# Processor.net
KiCad netlist of a schematic drawn in Altium Designer
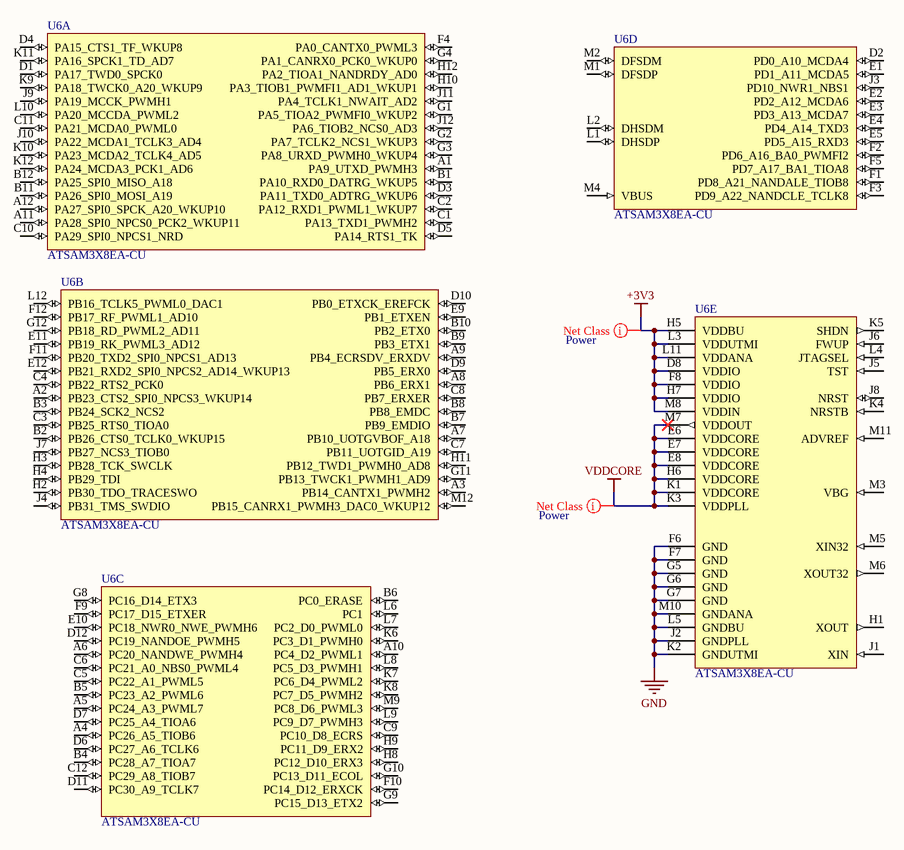
[diagram p0: Processor.SchDoc]

(export (version "E")
  (design (tool "Eeschema 10.0.6"))
  (components
    (comp (ref "U6")
      (value "ATSAM3X8EA-CU")
      (footprint "Atmel_LFBGA144_M")
      (libsource (lib "niceCircuits") (part "ATSAM3X8EA-CU"))
    )
  )
  (nets
    (net (code "1") (name "+3V3") (class "Default")
      (node (ref "U6") (pin "D8") (pinfunction "VDDIO_D8") (pintype "power_in"))
      (node (ref "U6") (pin "F8") (pinfunction "VDDIO_F8") (pintype "power_in"))
      (node (ref "U6") (pin "H5") (pinfunction "VDDBU_H5") (pintype "power_in"))
      (node (ref "U6") (pin "H7") (pinfunction "VDDIO_H7") (pintype "power_in"))
      (node (ref "U6") (pin "L11") (pinfunction "VDDANA_L11") (pintype "power_in"))
      (node (ref "U6") (pin "L3") (pinfunction "VDDUTMI_L3") (pintype "power_in"))
      (node (ref "U6") (pin "M8") (pinfunction "VDDIN_M8") (pintype "power_in"))
    )
    (net (code "2") (name "GND") (class "Default")
      (node (ref "U6") (pin "F6") (pinfunction "GND_F6") (pintype "power_in"))
      (node (ref "U6") (pin "F7") (pinfunction "GND_F7") (pintype "power_in"))
      (node (ref "U6") (pin "G5") (pinfunction "GND_G5") (pintype "power_in"))
      (node (ref "U6") (pin "G6") (pinfunction "GND_G6") (pintype "power_in"))
      (node (ref "U6") (pin "G7") (pinfunction "GND_G7") (pintype "power_in"))
      (node (ref "U6") (pin "J2") (pinfunction "GNDPLL_J2") (pintype "power_in"))
      (node (ref "U6") (pin "K2") (pinfunction "GNDUTMI_K2") (pintype "power_in"))
      (node (ref "U6") (pin "L5") (pinfunction "GNDBU_L5") (pintype "power_in"))
      (node (ref "U6") (pin "M10") (pinfunction "GNDANA_M10") (pintype "power_in"))
    )
    (net (code "3") (name "VDDCORE") (class "Default")
      (node (ref "U6") (pin "E6") (pinfunction "VDDCORE_E6") (pintype "power_in"))
      (node (ref "U6") (pin "E7") (pinfunction "VDDCORE_E7") (pintype "power_in"))
      (node (ref "U6") (pin "E8") (pinfunction "VDDCORE_E8") (pintype "power_in"))
      (node (ref "U6") (pin "H6") (pinfunction "VDDCORE_H6") (pintype "power_in"))
      (node (ref "U6") (pin "K1") (pinfunction "VDDCORE_K1") (pintype "power_in"))
      (node (ref "U6") (pin "K3") (pinfunction "VDDPLL_K3") (pintype "power_in"))
      (node (ref "U6") (pin "M7") (pinfunction "VDDOUT_M7") (pintype "output"))
    )
    (net (code "4") (name "unconnected-(U6A-PA0_CANTX0_PWML3-PadF4)") (class "Default")
      (node (ref "U6") (pin "F4") (pinfunction "PA0_CANTX0_PWML3_F4") (pintype "bidirectional"))
    )
    (net (code "5") (name "unconnected-(U6A-PA1_CANRX0_PCK0_WKUP0-PadG4)") (class "Default")
      (node (ref "U6") (pin "G4") (pinfunction "PA1_CANRX0_PCK0_WKUP0_G4") (pintype "bidirectional"))
    )
    (net (code "6") (name "unconnected-(U6A-PA2_TIOA1_NANDRDY_AD0-PadH12)") (class "Default")
      (node (ref "U6") (pin "H12") (pinfunction "PA2_TIOA1_NANDRDY_AD0_H12") (pintype "bidirectional"))
    )
    (net (code "7") (name "unconnected-(U6A-PA3_TIOB1_PWMFI1_AD1_WKUP1-PadH10)") (class "Default")
      (node (ref "U6") (pin "H10") (pinfunction "PA3_TIOB1_PWMFI1_AD1_WKUP1_H10") (pintype "bidirectional"))
    )
    (net (code "8") (name "unconnected-(U6A-PA4_TCLK1_NWAIT_AD2-PadJ11)") (class "Default")
      (node (ref "U6") (pin "J11") (pinfunction "PA4_TCLK1_NWAIT_AD2_J11") (pintype "bidirectional"))
    )
    (net (code "9") (name "unconnected-(U6A-PA5_TIOA2_PWMFI0_WKUP2-PadG1)") (class "Default")
      (node (ref "U6") (pin "G1") (pinfunction "PA5_TIOA2_PWMFI0_WKUP2_G1") (pintype "bidirectional"))
    )
    (net (code "10") (name "unconnected-(U6A-PA6_TIOB2_NCS0_AD3-PadJ12)") (class "Default")
      (node (ref "U6") (pin "J12") (pinfunction "PA6_TIOB2_NCS0_AD3_J12") (pintype "bidirectional"))
    )
    (net (code "11") (name "unconnected-(U6A-PA7_TCLK2_NCS1_WKUP3-PadG2)") (class "Default")
      (node (ref "U6") (pin "G2") (pinfunction "PA7_TCLK2_NCS1_WKUP3_G2") (pintype "bidirectional"))
    )
    (net (code "12") (name "unconnected-(U6A-PA8_URXD_PWMH0_WKUP4-PadG3)") (class "Default")
      (node (ref "U6") (pin "G3") (pinfunction "PA8_URXD_PWMH0_WKUP4_G3") (pintype "bidirectional"))
    )
    (net (code "13") (name "unconnected-(U6A-PA9_UTXD_PWMH3-PadA1)") (class "Default")
      (node (ref "U6") (pin "A1") (pinfunction "PA9_UTXD_PWMH3_A1") (pintype "bidirectional"))
    )
    (net (code "14") (name "unconnected-(U6A-PA10_RXD0_DATRG_WKUP5-PadB1)") (class "Default")
      (node (ref "U6") (pin "B1") (pinfunction "PA10_RXD0_DATRG_WKUP5_B1") (pintype "bidirectional"))
    )
    (net (code "15") (name "unconnected-(U6A-PA11_TXD0_ADTRG_WKUP6-PadD3)") (class "Default")
      (node (ref "U6") (pin "D3") (pinfunction "PA11_TXD0_ADTRG_WKUP6_D3") (pintype "bidirectional"))
    )
    (net (code "16") (name "unconnected-(U6A-PA12_RXD1_PWML1_WKUP7-PadC2)") (class "Default")
      (node (ref "U6") (pin "C2") (pinfunction "PA12_RXD1_PWML1_WKUP7_C2") (pintype "bidirectional"))
    )
    (net (code "17") (name "unconnected-(U6A-PA13_TXD1_PWMH2-PadC1)") (class "Default")
      (node (ref "U6") (pin "C1") (pinfunction "PA13_TXD1_PWMH2_C1") (pintype "bidirectional"))
    )
    (net (code "18") (name "unconnected-(U6A-PA14_RTS1_TK-PadD5)") (class "Default")
      (node (ref "U6") (pin "D5") (pinfunction "PA14_RTS1_TK_D5") (pintype "bidirectional"))
    )
    (net (code "19") (name "unconnected-(U6A-PA15_CTS1_TF_WKUP8-PadD4)") (class "Default")
      (node (ref "U6") (pin "D4") (pinfunction "PA15_CTS1_TF_WKUP8_D4") (pintype "bidirectional"))
    )
    (net (code "20") (name "unconnected-(U6A-PA16_SPCK1_TD_AD7-PadK11)") (class "Default")
      (node (ref "U6") (pin "K11") (pinfunction "PA16_SPCK1_TD_AD7_K11") (pintype "bidirectional"))
    )
    (net (code "21") (name "unconnected-(U6A-PA17_TWD0_SPCK0-PadD1)") (class "Default")
      (node (ref "U6") (pin "D1") (pinfunction "PA17_TWD0_SPCK0_D1") (pintype "bidirectional"))
    )
    (net (code "22") (name "unconnected-(U6A-PA18_TWCK0_A20_WKUP9-PadK9)") (class "Default")
      (node (ref "U6") (pin "K9") (pinfunction "PA18_TWCK0_A20_WKUP9_K9") (pintype "bidirectional"))
    )
    (net (code "23") (name "unconnected-(U6A-PA19_MCCK_PWMH1-PadJ9)") (class "Default")
      (node (ref "U6") (pin "J9") (pinfunction "PA19_MCCK_PWMH1_J9") (pintype "bidirectional"))
    )
    (net (code "24") (name "unconnected-(U6A-PA20_MCCDA_PWML2-PadL10)") (class "Default")
      (node (ref "U6") (pin "L10") (pinfunction "PA20_MCCDA_PWML2_L10") (pintype "bidirectional"))
    )
    (net (code "25") (name "unconnected-(U6A-PA21_MCDA0_PWML0-PadC11)") (class "Default")
      (node (ref "U6") (pin "C11") (pinfunction "PA21_MCDA0_PWML0_C11") (pintype "bidirectional"))
    )
    (net (code "26") (name "unconnected-(U6A-PA22_MCDA1_TCLK3_AD4-PadJ10)") (class "Default")
      (node (ref "U6") (pin "J10") (pinfunction "PA22_MCDA1_TCLK3_AD4_J10") (pintype "bidirectional"))
    )
    (net (code "27") (name "unconnected-(U6A-PA23_MCDA2_TCLK4_AD5-PadK10)") (class "Default")
      (node (ref "U6") (pin "K10") (pinfunction "PA23_MCDA2_TCLK4_AD5_K10") (pintype "bidirectional"))
    )
    (net (code "28") (name "unconnected-(U6A-PA24_MCDA3_PCK1_AD6-PadK12)") (class "Default")
      (node (ref "U6") (pin "K12") (pinfunction "PA24_MCDA3_PCK1_AD6_K12") (pintype "bidirectional"))
    )
    (net (code "29") (name "unconnected-(U6A-PA25_SPI0_MISO_A18-PadB12)") (class "Default")
      (node (ref "U6") (pin "B12") (pinfunction "PA25_SPI0_MISO_A18_B12") (pintype "bidirectional"))
    )
    (net (code "30") (name "unconnected-(U6A-PA26_SPI0_MOSI_A19-PadB11)") (class "Default")
      (node (ref "U6") (pin "B11") (pinfunction "PA26_SPI0_MOSI_A19_B11") (pintype "bidirectional"))
    )
    (net (code "31") (name "unconnected-(U6A-PA27_SPI0_SPCK_A20_WKUP10-PadA12)") (class "Default")
      (node (ref "U6") (pin "A12") (pinfunction "PA27_SPI0_SPCK_A20_WKUP10_A12") (pintype "bidirectional"))
    )
    (net (code "32") (name "unconnected-(U6A-PA28_SPI0_NPCS0_PCK2_WKUP11-PadA11)") (class "Default")
      (node (ref "U6") (pin "A11") (pinfunction "PA28_SPI0_NPCS0_PCK2_WKUP11_A11") (pintype "bidirectional"))
    )
    (net (code "33") (name "unconnected-(U6A-PA29_SPI0_NPCS1_NRD-PadC10)") (class "Default")
      (node (ref "U6") (pin "C10") (pinfunction "PA29_SPI0_NPCS1_NRD_C10") (pintype "bidirectional"))
    )
    (net (code "34") (name "unconnected-(U6B-PB0_ETXCK_EREFCK-PadD10)") (class "Default")
      (node (ref "U6") (pin "D10") (pinfunction "PB0_ETXCK_EREFCK_D10") (pintype "bidirectional"))
    )
    (net (code "35") (name "unconnected-(U6B-PB1_ETXEN-PadE9)") (class "Default")
      (node (ref "U6") (pin "E9") (pinfunction "PB1_ETXEN_E9") (pintype "bidirectional"))
    )
    (net (code "36") (name "unconnected-(U6B-PB2_ETX0-PadB10)") (class "Default")
      (node (ref "U6") (pin "B10") (pinfunction "PB2_ETX0_B10") (pintype "bidirectional"))
    )
    (net (code "37") (name "unconnected-(U6B-PB3_ETX1-PadB9)") (class "Default")
      (node (ref "U6") (pin "B9") (pinfunction "PB3_ETX1_B9") (pintype "bidirectional"))
    )
    (net (code "38") (name "unconnected-(U6B-PB4_ECRSDV_ERXDV-PadA9)") (class "Default")
      (node (ref "U6") (pin "A9") (pinfunction "PB4_ECRSDV_ERXDV_A9") (pintype "bidirectional"))
    )
    (net (code "39") (name "unconnected-(U6B-PB5_ERX0-PadD9)") (class "Default")
      (node (ref "U6") (pin "D9") (pinfunction "PB5_ERX0_D9") (pintype "bidirectional"))
    )
    (net (code "40") (name "unconnected-(U6B-PB6_ERX1-PadA8)") (class "Default")
      (node (ref "U6") (pin "A8") (pinfunction "PB6_ERX1_A8") (pintype "bidirectional"))
    )
    (net (code "41") (name "unconnected-(U6B-PB7_ERXER-PadC8)") (class "Default")
      (node (ref "U6") (pin "C8") (pinfunction "PB7_ERXER_C8") (pintype "bidirectional"))
    )
    (net (code "42") (name "unconnected-(U6B-PB8_EMDC-PadB8)") (class "Default")
      (node (ref "U6") (pin "B8") (pinfunction "PB8_EMDC_B8") (pintype "bidirectional"))
    )
    (net (code "43") (name "unconnected-(U6B-PB9_EMDIO-PadB7)") (class "Default")
      (node (ref "U6") (pin "B7") (pinfunction "PB9_EMDIO_B7") (pintype "bidirectional"))
    )
    (net (code "44") (name "unconnected-(U6B-PB10_UOTGVBOF_A18-PadA7)") (class "Default")
      (node (ref "U6") (pin "A7") (pinfunction "PB10_UOTGVBOF_A18_A7") (pintype "bidirectional"))
    )
    (net (code "45") (name "unconnected-(U6B-PB11_UOTGID_A19-PadC7)") (class "Default")
      (node (ref "U6") (pin "C7") (pinfunction "PB11_UOTGID_A19_C7") (pintype "bidirectional"))
    )
    (net (code "46") (name "unconnected-(U6B-PB12_TWD1_PWMH0_AD8-PadH11)") (class "Default")
      (node (ref "U6") (pin "H11") (pinfunction "PB12_TWD1_PWMH0_AD8_H11") (pintype "bidirectional"))
    )
    (net (code "47") (name "unconnected-(U6B-PB13_TWCK1_PWMH1_AD9-PadG11)") (class "Default")
      (node (ref "U6") (pin "G11") (pinfunction "PB13_TWCK1_PWMH1_AD9_G11") (pintype "bidirectional"))
    )
    (net (code "48") (name "unconnected-(U6B-PB14_CANTX1_PWMH2-PadA3)") (class "Default")
      (node (ref "U6") (pin "A3") (pinfunction "PB14_CANTX1_PWMH2_A3") (pintype "bidirectional"))
    )
    (net (code "49") (name "unconnected-(U6B-PB15_CANRX1_PWMH3_DAC0_WKUP12-PadM12)") (class "Default")
      (node (ref "U6") (pin "M12") (pinfunction "PB15_CANRX1_PWMH3_DAC0_WKUP12_M12") (pintype "bidirectional"))
    )
    (net (code "50") (name "unconnected-(U6B-PB16_TCLK5_PWML0_DAC1-PadL12)") (class "Default")
      (node (ref "U6") (pin "L12") (pinfunction "PB16_TCLK5_PWML0_DAC1_L12") (pintype "bidirectional"))
    )
    (net (code "51") (name "unconnected-(U6B-PB17_RF_PWML1_AD10-PadF12)") (class "Default")
      (node (ref "U6") (pin "F12") (pinfunction "PB17_RF_PWML1_AD10_F12") (pintype "bidirectional"))
    )
    (net (code "52") (name "unconnected-(U6B-PB18_RD_PWML2_AD11-PadG12)") (class "Default")
      (node (ref "U6") (pin "G12") (pinfunction "PB18_RD_PWML2_AD11_G12") (pintype "bidirectional"))
    )
    (net (code "53") (name "unconnected-(U6B-PB19_RK_PWML3_AD12-PadE11)") (class "Default")
      (node (ref "U6") (pin "E11") (pinfunction "PB19_RK_PWML3_AD12_E11") (pintype "bidirectional"))
    )
    (net (code "54") (name "unconnected-(U6B-PB20_TXD2_SPI0_NPCS1_AD13-PadF11)") (class "Default")
      (node (ref "U6") (pin "F11") (pinfunction "PB20_TXD2_SPI0_NPCS1_AD13_F11") (pintype "bidirectional"))
    )
    (net (code "55") (name "unconnected-(U6B-PB21_RXD2_SPI0_NPCS2_AD14_WKUP13-PadE12)") (class "Default")
      (node (ref "U6") (pin "E12") (pinfunction "PB21_RXD2_SPI0_NPCS2_AD14_WKUP13_E12") (pintype "bidirectional"))
    )
    (net (code "56") (name "unconnected-(U6B-PB22_RTS2_PCK0-PadC4)") (class "Default")
      (node (ref "U6") (pin "C4") (pinfunction "PB22_RTS2_PCK0_C4") (pintype "bidirectional"))
    )
    (net (code "57") (name "unconnected-(U6B-PB23_CTS2_SPI0_NPCS3_WKUP14-PadA2)") (class "Default")
      (node (ref "U6") (pin "A2") (pinfunction "PB23_CTS2_SPI0_NPCS3_WKUP14_A2") (pintype "bidirectional"))
    )
    (net (code "58") (name "unconnected-(U6B-PB24_SCK2_NCS2-PadB3)") (class "Default")
      (node (ref "U6") (pin "B3") (pinfunction "PB24_SCK2_NCS2_B3") (pintype "bidirectional"))
    )
    (net (code "59") (name "unconnected-(U6B-PB25_RTS0_TIOA0-PadC3)") (class "Default")
      (node (ref "U6") (pin "C3") (pinfunction "PB25_RTS0_TIOA0_C3") (pintype "bidirectional"))
    )
    (net (code "60") (name "unconnected-(U6B-PB26_CTS0_TCLK0_WKUP15-PadB2)") (class "Default")
      (node (ref "U6") (pin "B2") (pinfunction "PB26_CTS0_TCLK0_WKUP15_B2") (pintype "bidirectional"))
    )
    (net (code "61") (name "unconnected-(U6B-PB27_NCS3_TIOB0-PadJ7)") (class "Default")
      (node (ref "U6") (pin "J7") (pinfunction "PB27_NCS3_TIOB0_J7") (pintype "bidirectional"))
    )
    (net (code "62") (name "unconnected-(U6B-PB28_TCK_SWCLK-PadH3)") (class "Default")
      (node (ref "U6") (pin "H3") (pinfunction "PB28_TCK_SWCLK_H3") (pintype "bidirectional"))
    )
    (net (code "63") (name "unconnected-(U6B-PB29_TDI-PadH4)") (class "Default")
      (node (ref "U6") (pin "H4") (pinfunction "PB29_TDI_H4") (pintype "bidirectional"))
    )
    (net (code "64") (name "unconnected-(U6B-PB30_TDO_TRACESWO-PadH2)") (class "Default")
      (node (ref "U6") (pin "H2") (pinfunction "PB30_TDO_TRACESWO_H2") (pintype "bidirectional"))
    )
    (net (code "65") (name "unconnected-(U6B-PB31_TMS_SWDIO-PadJ4)") (class "Default")
      (node (ref "U6") (pin "J4") (pinfunction "PB31_TMS_SWDIO_J4") (pintype "bidirectional"))
    )
    (net (code "66") (name "unconnected-(U6C-PC0_ERASE-PadB6)") (class "Default")
      (node (ref "U6") (pin "B6") (pinfunction "PC0_ERASE_B6") (pintype "bidirectional"))
    )
    (net (code "67") (name "unconnected-(U6C-PC1-PadL6)") (class "Default")
      (node (ref "U6") (pin "L6") (pinfunction "PC1_L6") (pintype "bidirectional"))
    )
    (net (code "68") (name "unconnected-(U6C-PC2_D0_PWML0-PadL7)") (class "Default")
      (node (ref "U6") (pin "L7") (pinfunction "PC2_D0_PWML0_L7") (pintype "bidirectional"))
    )
    (net (code "69") (name "unconnected-(U6C-PC3_D1_PWMH0-PadK6)") (class "Default")
      (node (ref "U6") (pin "K6") (pinfunction "PC3_D1_PWMH0_K6") (pintype "bidirectional"))
    )
    (net (code "70") (name "unconnected-(U6C-PC4_D2_PWML1-PadA10)") (class "Default")
      (node (ref "U6") (pin "A10") (pinfunction "PC4_D2_PWML1_A10") (pintype "bidirectional"))
    )
    (net (code "71") (name "unconnected-(U6C-PC5_D3_PWMH1-PadL8)") (class "Default")
      (node (ref "U6") (pin "L8") (pinfunction "PC5_D3_PWMH1_L8") (pintype "bidirectional"))
    )
    (net (code "72") (name "unconnected-(U6C-PC6_D4_PWML2-PadK7)") (class "Default")
      (node (ref "U6") (pin "K7") (pinfunction "PC6_D4_PWML2_K7") (pintype "bidirectional"))
    )
    (net (code "73") (name "unconnected-(U6C-PC7_D5_PWMH2-PadK8)") (class "Default")
      (node (ref "U6") (pin "K8") (pinfunction "PC7_D5_PWMH2_K8") (pintype "bidirectional"))
    )
    (net (code "74") (name "unconnected-(U6C-PC8_D6_PWML3-PadM9)") (class "Default")
      (node (ref "U6") (pin "M9") (pinfunction "PC8_D6_PWML3_M9") (pintype "bidirectional"))
    )
    (net (code "75") (name "unconnected-(U6C-PC9_D7_PWMH3-PadL9)") (class "Default")
      (node (ref "U6") (pin "L9") (pinfunction "PC9_D7_PWMH3_L9") (pintype "bidirectional"))
    )
    (net (code "76") (name "unconnected-(U6C-PC10_D8_ECRS-PadC9)") (class "Default")
      (node (ref "U6") (pin "C9") (pinfunction "PC10_D8_ECRS_C9") (pintype "bidirectional"))
    )
    (net (code "77") (name "unconnected-(U6C-PC11_D9_ERX2-PadH9)") (class "Default")
      (node (ref "U6") (pin "H9") (pinfunction "PC11_D9_ERX2_H9") (pintype "bidirectional"))
    )
    (net (code "78") (name "unconnected-(U6C-PC12_D10_ERX3-PadH8)") (class "Default")
      (node (ref "U6") (pin "H8") (pinfunction "PC12_D10_ERX3_H8") (pintype "bidirectional"))
    )
    (net (code "79") (name "unconnected-(U6C-PC13_D11_ECOL-PadG10)") (class "Default")
      (node (ref "U6") (pin "G10") (pinfunction "PC13_D11_ECOL_G10") (pintype "bidirectional"))
    )
    (net (code "80") (name "unconnected-(U6C-PC14_D12_ERXCK-PadF10)") (class "Default")
      (node (ref "U6") (pin "F10") (pinfunction "PC14_D12_ERXCK_F10") (pintype "bidirectional"))
    )
    (net (code "81") (name "unconnected-(U6C-PC15_D13_ETX2-PadG9)") (class "Default")
      (node (ref "U6") (pin "G9") (pinfunction "PC15_D13_ETX2_G9") (pintype "bidirectional"))
    )
    (net (code "82") (name "unconnected-(U6C-PC16_D14_ETX3-PadG8)") (class "Default")
      (node (ref "U6") (pin "G8") (pinfunction "PC16_D14_ETX3_G8") (pintype "bidirectional"))
    )
    (net (code "83") (name "unconnected-(U6C-PC17_D15_ETXER-PadF9)") (class "Default")
      (node (ref "U6") (pin "F9") (pinfunction "PC17_D15_ETXER_F9") (pintype "bidirectional"))
    )
    (net (code "84") (name "unconnected-(U6C-PC18_NWR0_NWE_PWMH6-PadE10)") (class "Default")
      (node (ref "U6") (pin "E10") (pinfunction "PC18_NWR0_NWE_PWMH6_E10") (pintype "bidirectional"))
    )
    (net (code "85") (name "unconnected-(U6C-PC19_NANDOE_PWMH5-PadD12)") (class "Default")
      (node (ref "U6") (pin "D12") (pinfunction "PC19_NANDOE_PWMH5_D12") (pintype "bidirectional"))
    )
    (net (code "86") (name "unconnected-(U6C-PC20_NANDWE_PWMH4-PadA6)") (class "Default")
      (node (ref "U6") (pin "A6") (pinfunction "PC20_NANDWE_PWMH4_A6") (pintype "bidirectional"))
    )
    (net (code "87") (name "unconnected-(U6C-PC21_A0_NBS0_PWML4-PadC6)") (class "Default")
      (node (ref "U6") (pin "C6") (pinfunction "PC21_A0_NBS0_PWML4_C6") (pintype "bidirectional"))
    )
    (net (code "88") (name "unconnected-(U6C-PC22_A1_PWML5-PadC5)") (class "Default")
      (node (ref "U6") (pin "C5") (pinfunction "PC22_A1_PWML5_C5") (pintype "bidirectional"))
    )
    (net (code "89") (name "unconnected-(U6C-PC23_A2_PWML6-PadB5)") (class "Default")
      (node (ref "U6") (pin "B5") (pinfunction "PC23_A2_PWML6_B5") (pintype "bidirectional"))
    )
    (net (code "90") (name "unconnected-(U6C-PC24_A3_PWML7-PadA5)") (class "Default")
      (node (ref "U6") (pin "A5") (pinfunction "PC24_A3_PWML7_A5") (pintype "bidirectional"))
    )
    (net (code "91") (name "unconnected-(U6C-PC25_A4_TIOA6-PadD7)") (class "Default")
      (node (ref "U6") (pin "D7") (pinfunction "PC25_A4_TIOA6_D7") (pintype "bidirectional"))
    )
    (net (code "92") (name "unconnected-(U6C-PC26_A5_TIOB6-PadA4)") (class "Default")
      (node (ref "U6") (pin "A4") (pinfunction "PC26_A5_TIOB6_A4") (pintype "bidirectional"))
    )
    (net (code "93") (name "unconnected-(U6C-PC27_A6_TCLK6-PadD6)") (class "Default")
      (node (ref "U6") (pin "D6") (pinfunction "PC27_A6_TCLK6_D6") (pintype "bidirectional"))
    )
    (net (code "94") (name "unconnected-(U6C-PC28_A7_TIOA7-PadB4)") (class "Default")
      (node (ref "U6") (pin "B4") (pinfunction "PC28_A7_TIOA7_B4") (pintype "bidirectional"))
    )
    (net (code "95") (name "unconnected-(U6C-PC29_A8_TIOB7-PadC12)") (class "Default")
      (node (ref "U6") (pin "C12") (pinfunction "PC29_A8_TIOB7_C12") (pintype "bidirectional"))
    )
    (net (code "96") (name "unconnected-(U6C-PC30_A9_TCLK7-PadD11)") (class "Default")
      (node (ref "U6") (pin "D11") (pinfunction "PC30_A9_TCLK7_D11") (pintype "bidirectional"))
    )
    (net (code "97") (name "unconnected-(U6D-DFSDM-PadM2)") (class "Default")
      (node (ref "U6") (pin "M2") (pinfunction "DFSDM_M2") (pintype "bidirectional"))
    )
    (net (code "98") (name "unconnected-(U6D-DFSDP-PadM1)") (class "Default")
      (node (ref "U6") (pin "M1") (pinfunction "DFSDP_M1") (pintype "bidirectional"))
    )
    (net (code "99") (name "unconnected-(U6D-DHSDM-PadL2)") (class "Default")
      (node (ref "U6") (pin "L2") (pinfunction "DHSDM_L2") (pintype "bidirectional"))
    )
    (net (code "100") (name "unconnected-(U6D-DHSDP-PadL1)") (class "Default")
      (node (ref "U6") (pin "L1") (pinfunction "DHSDP_L1") (pintype "bidirectional"))
    )
    (net (code "101") (name "unconnected-(U6D-PD0_A10_MCDA4-PadD2)") (class "Default")
      (node (ref "U6") (pin "D2") (pinfunction "PD0_A10_MCDA4_D2") (pintype "bidirectional"))
    )
    (net (code "102") (name "unconnected-(U6D-PD1_A11_MCDA5-PadE1)") (class "Default")
      (node (ref "U6") (pin "E1") (pinfunction "PD1_A11_MCDA5_E1") (pintype "bidirectional"))
    )
    (net (code "103") (name "unconnected-(U6D-PD2_A12_MCDA6-PadE2)") (class "Default")
      (node (ref "U6") (pin "E2") (pinfunction "PD2_A12_MCDA6_E2") (pintype "bidirectional"))
    )
    (net (code "104") (name "unconnected-(U6D-PD3_A13_MCDA7-PadE3)") (class "Default")
      (node (ref "U6") (pin "E3") (pinfunction "PD3_A13_MCDA7_E3") (pintype "bidirectional"))
    )
    (net (code "105") (name "unconnected-(U6D-PD4_A14_TXD3-PadE4)") (class "Default")
      (node (ref "U6") (pin "E4") (pinfunction "PD4_A14_TXD3_E4") (pintype "bidirectional"))
    )
    (net (code "106") (name "unconnected-(U6D-PD5_A15_RXD3-PadE5)") (class "Default")
      (node (ref "U6") (pin "E5") (pinfunction "PD5_A15_RXD3_E5") (pintype "bidirectional"))
    )
    (net (code "107") (name "unconnected-(U6D-PD6_A16_BA0_PWMFI2-PadF2)") (class "Default")
      (node (ref "U6") (pin "F2") (pinfunction "PD6_A16_BA0_PWMFI2_F2") (pintype "bidirectional"))
    )
    (net (code "108") (name "unconnected-(U6D-PD7_A17_BA1_TIOA8-PadF5)") (class "Default")
      (node (ref "U6") (pin "F5") (pinfunction "PD7_A17_BA1_TIOA8_F5") (pintype "bidirectional"))
    )
    (net (code "109") (name "unconnected-(U6D-PD8_A21_NANDALE_TIOB8-PadF1)") (class "Default")
      (node (ref "U6") (pin "F1") (pinfunction "PD8_A21_NANDALE_TIOB8_F1") (pintype "bidirectional"))
    )
    (net (code "110") (name "unconnected-(U6D-PD9_A22_NANDCLE_TCLK8-PadF3)") (class "Default")
      (node (ref "U6") (pin "F3") (pinfunction "PD9_A22_NANDCLE_TCLK8_F3") (pintype "bidirectional"))
    )
    (net (code "111") (name "unconnected-(U6D-PD10_NWR1_NBS1-PadJ3)") (class "Default")
      (node (ref "U6") (pin "J3") (pinfunction "PD10_NWR1_NBS1_J3") (pintype "bidirectional"))
    )
    (net (code "112") (name "unconnected-(U6D-VBUS-PadM4)") (class "Default")
      (node (ref "U6") (pin "M4") (pinfunction "VBUS_M4") (pintype "input"))
    )
    (net (code "113") (name "unconnected-(U6E-ADVREF-PadM11)") (class "Default")
      (node (ref "U6") (pin "M11") (pinfunction "ADVREF_M11") (pintype "input"))
    )
    (net (code "114") (name "unconnected-(U6E-FWUP-PadJ6)") (class "Default")
      (node (ref "U6") (pin "J6") (pinfunction "FWUP_J6") (pintype "input"))
    )
    (net (code "115") (name "unconnected-(U6E-JTAGSEL-PadL4)") (class "Default")
      (node (ref "U6") (pin "L4") (pinfunction "JTAGSEL_L4") (pintype "input"))
    )
    (net (code "116") (name "unconnected-(U6E-NRST-PadJ8)") (class "Default")
      (node (ref "U6") (pin "J8") (pinfunction "NRST_J8") (pintype "bidirectional"))
    )
    (net (code "117") (name "unconnected-(U6E-NRSTB-PadK4)") (class "Default")
      (node (ref "U6") (pin "K4") (pinfunction "NRSTB_K4") (pintype "input"))
    )
    (net (code "118") (name "unconnected-(U6E-SHDN-PadK5)") (class "Default")
      (node (ref "U6") (pin "K5") (pinfunction "SHDN_K5") (pintype "output"))
    )
    (net (code "119") (name "unconnected-(U6E-TST-PadJ5)") (class "Default")
      (node (ref "U6") (pin "J5") (pinfunction "TST_J5") (pintype "input"))
    )
    (net (code "120") (name "unconnected-(U6E-VBG-PadM3)") (class "Default")
      (node (ref "U6") (pin "M3") (pinfunction "VBG_M3") (pintype "input"))
    )
    (net (code "121") (name "unconnected-(U6E-XIN-PadJ1)") (class "Default")
      (node (ref "U6") (pin "J1") (pinfunction "XIN_J1") (pintype "input"))
    )
    (net (code "122") (name "unconnected-(U6E-XIN32-PadM5)") (class "Default")
      (node (ref "U6") (pin "M5") (pinfunction "XIN32_M5") (pintype "input"))
    )
    (net (code "123") (name "unconnected-(U6E-XOUT-PadH1)") (class "Default")
      (node (ref "U6") (pin "H1") (pinfunction "XOUT_H1") (pintype "output"))
    )
    (net (code "124") (name "unconnected-(U6E-XOUT32-PadM6)") (class "Default")
      (node (ref "U6") (pin "M6") (pinfunction "XOUT32_M6") (pintype "output"))
    )
  )
)
